# TRAY5.net
KiCad netlist of a schematic drawn in Altium Designer
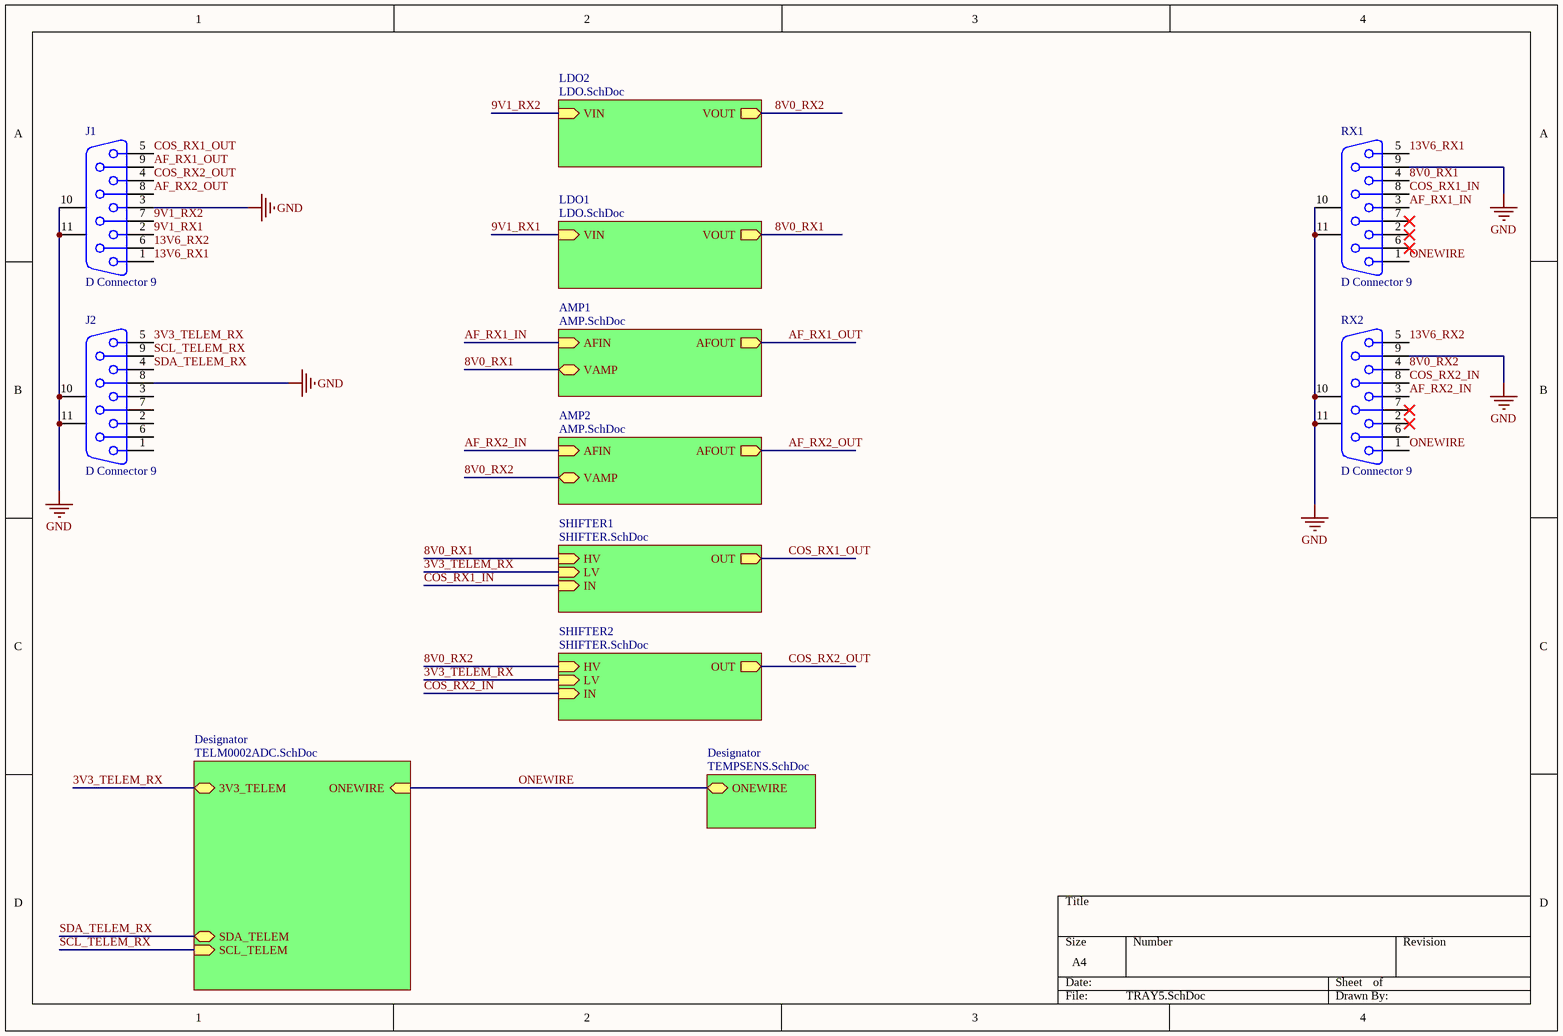
[diagram p0: TRAY5.SchDoc]

(export (version "E")
  (design (tool "Eeschema 10.0.6"))
  (components
    (comp (ref "J1")
      (value "D Connector 9")
      (footprint "DSUB1.385-2H9")
      (description "Receptacle Assembly, 9 Position, Right Angle")
      (libsource (lib "Miscellaneous Connectors") (part "D Connector 9"))
    )
    (comp (ref "J2")
      (value "D Connector 9")
      (footprint "DSUB1.385-2H9")
      (description "Receptacle Assembly, 9 Position, Right Angle")
      (libsource (lib "Miscellaneous Connectors") (part "D Connector 9"))
    )
    (comp (ref "RX1")
      (value "D Connector 9")
      (footprint "DSUB Upright")
      (description "Receptacle Assembly, 9 Position, Upright")
      (libsource (lib "Miscellaneous Connectors") (part "D Connector 9"))
    )
    (comp (ref "RX2")
      (value "D Connector 9")
      (footprint "DSUB Upright")
      (description "Receptacle Assembly, 9 Position, Upright")
      (libsource (lib "Miscellaneous Connectors") (part "D Connector 9"))
    )
  )
  (nets
    (net (code "1") (name "/3V3_TELEM_RX") (class "Default")
      (node (ref "J2") (pin "5") (pinfunction "5_5") (pintype "passive"))
    )
    (net (code "2") (name "/8V0_RX1") (class "Default")
      (node (ref "RX1") (pin "4") (pinfunction "4_4") (pintype "passive"))
    )
    (net (code "3") (name "/8V0_RX2") (class "Default")
      (node (ref "RX2") (pin "4") (pinfunction "4_4") (pintype "passive"))
    )
    (net (code "4") (name "/9V1_RX1") (class "Default")
      (node (ref "J1") (pin "2") (pinfunction "2_2") (pintype "passive"))
    )
    (net (code "5") (name "/9V1_RX2") (class "Default")
      (node (ref "J1") (pin "7") (pinfunction "7_7") (pintype "passive"))
    )
    (net (code "6") (name "/13V6_RX1") (class "Default")
      (node (ref "J1") (pin "1") (pinfunction "1_1") (pintype "passive"))
      (node (ref "RX1") (pin "5") (pinfunction "5_5") (pintype "passive"))
    )
    (net (code "7") (name "/13V6_RX2") (class "Default")
      (node (ref "J1") (pin "6") (pinfunction "6_6") (pintype "passive"))
      (node (ref "RX2") (pin "5") (pinfunction "5_5") (pintype "passive"))
    )
    (net (code "8") (name "/AF_RX1_IN") (class "Default")
      (node (ref "RX1") (pin "3") (pinfunction "3_3") (pintype "passive"))
    )
    (net (code "9") (name "/AF_RX1_OUT") (class "Default")
      (node (ref "J1") (pin "9") (pinfunction "9_9") (pintype "passive"))
    )
    (net (code "10") (name "/AF_RX2_IN") (class "Default")
      (node (ref "RX2") (pin "3") (pinfunction "3_3") (pintype "passive"))
    )
    (net (code "11") (name "/AF_RX2_OUT") (class "Default")
      (node (ref "J1") (pin "8") (pinfunction "8_8") (pintype "passive"))
    )
    (net (code "12") (name "/COS_RX1_IN") (class "Default")
      (node (ref "RX1") (pin "8") (pinfunction "8_8") (pintype "passive"))
    )
    (net (code "13") (name "/COS_RX1_OUT") (class "Default")
      (node (ref "J1") (pin "5") (pinfunction "5_5") (pintype "passive"))
    )
    (net (code "14") (name "/COS_RX2_IN") (class "Default")
      (node (ref "RX2") (pin "8") (pinfunction "8_8") (pintype "passive"))
    )
    (net (code "15") (name "/COS_RX2_OUT") (class "Default")
      (node (ref "J1") (pin "4") (pinfunction "4_4") (pintype "passive"))
    )
    (net (code "16") (name "/ONEWIRE") (class "Default")
      (node (ref "RX1") (pin "1") (pinfunction "1_1") (pintype "passive"))
      (node (ref "RX2") (pin "1") (pinfunction "1_1") (pintype "passive"))
    )
    (net (code "17") (name "/SCL_TELEM_RX") (class "Default")
      (node (ref "J2") (pin "9") (pinfunction "9_9") (pintype "passive"))
    )
    (net (code "18") (name "/SDA_TELEM_RX") (class "Default")
      (node (ref "J2") (pin "4") (pinfunction "4_4") (pintype "passive"))
    )
    (net (code "19") (name "GND") (class "Default")
      (node (ref "J1") (pin "10") (pinfunction "MH1_10") (pintype "passive"))
      (node (ref "J1") (pin "11") (pinfunction "MH2_11") (pintype "passive"))
      (node (ref "J1") (pin "3") (pinfunction "3_3") (pintype "passive"))
      (node (ref "J2") (pin "10") (pinfunction "MH1_10") (pintype "passive"))
      (node (ref "J2") (pin "11") (pinfunction "MH2_11") (pintype "passive"))
      (node (ref "J2") (pin "8") (pinfunction "8_8") (pintype "passive"))
      (node (ref "RX1") (pin "10") (pinfunction "MH1_10") (pintype "passive"))
      (node (ref "RX1") (pin "11") (pinfunction "MH2_11") (pintype "passive"))
      (node (ref "RX1") (pin "9") (pinfunction "9_9") (pintype "passive"))
      (node (ref "RX2") (pin "10") (pinfunction "MH1_10") (pintype "passive"))
      (node (ref "RX2") (pin "11") (pinfunction "MH2_11") (pintype "passive"))
      (node (ref "RX2") (pin "9") (pinfunction "9_9") (pintype "passive"))
    )
    (net (code "20") (name "unconnected-(J2-Pad1)") (class "Default")
      (node (ref "J2") (pin "1") (pinfunction "1_1") (pintype "passive"))
    )
    (net (code "21") (name "unconnected-(J2-Pad2)") (class "Default")
      (node (ref "J2") (pin "2") (pinfunction "2_2") (pintype "passive"))
    )
    (net (code "22") (name "unconnected-(J2-Pad3)") (class "Default")
      (node (ref "J2") (pin "3") (pinfunction "3_3") (pintype "passive"))
    )
    (net (code "23") (name "unconnected-(J2-Pad6)") (class "Default")
      (node (ref "J2") (pin "6") (pinfunction "6_6") (pintype "passive"))
    )
    (net (code "24") (name "unconnected-(J2-Pad7)") (class "Default")
      (node (ref "J2") (pin "7") (pinfunction "7_7") (pintype "passive"))
    )
    (net (code "25") (name "unconnected-(RX1-Pad2)") (class "Default")
      (node (ref "RX1") (pin "2") (pinfunction "2_2") (pintype "passive+no_connect"))
    )
    (net (code "26") (name "unconnected-(RX1-Pad6)") (class "Default")
      (node (ref "RX1") (pin "6") (pinfunction "6_6") (pintype "passive+no_connect"))
    )
    (net (code "27") (name "unconnected-(RX1-Pad7)") (class "Default")
      (node (ref "RX1") (pin "7") (pinfunction "7_7") (pintype "passive+no_connect"))
    )
    (net (code "28") (name "unconnected-(RX2-Pad2)") (class "Default")
      (node (ref "RX2") (pin "2") (pinfunction "2_2") (pintype "passive+no_connect"))
    )
    (net (code "29") (name "unconnected-(RX2-Pad6)") (class "Default")
      (node (ref "RX2") (pin "6") (pinfunction "6_6") (pintype "passive"))
    )
    (net (code "30") (name "unconnected-(RX2-Pad7)") (class "Default")
      (node (ref "RX2") (pin "7") (pinfunction "7_7") (pintype "passive+no_connect"))
    )
  )
)
